# buzzer.net
KiCad netlist of a schematic drawn in Altium Designer
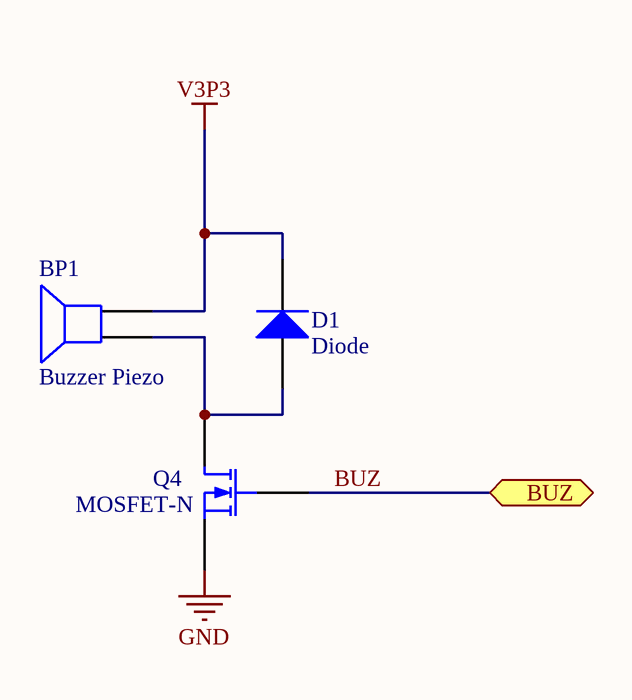
[diagram p0: buzzer.SchDoc]

(export (version "E")
  (design (tool "Eeschema 10.0.6"))
  (components
    (comp (ref "BP1")
      (value "Buzzer Piezo")
      (footprint "BUZZER")
      (description "Buzzer piezo")
      (fields (field (name "PUBLISHER") "Altium Limited"))
      (libsource (lib "Miscellaneous Devices") (part "Speaker"))
    )
    (comp (ref "D1")
      (value "Diode")
      (footprint "PONT REDRESSEUR")
      (description "Default Diode")
      (fields (field (name "PUBLISHER") "Altium Limited"))
      (libsource (lib "Miscellaneous Devices") (part "Diode"))
    )
    (comp (ref "Q4")
      (value "MOSFET-N")
      (footprint "MOSFET")
      (description "N-Channel MOSFET")
      (fields (field (name "PUBLISHER") "Altium Limited"))
      (libsource (lib "Miscellaneous Devices") (part "MOSFET-N"))
    )
  )
  (nets
    (net (code "1") (name "/BUZ") (class "Default")
      (node (ref "Q4") (pin "2") (pinfunction "G_2") (pintype "passive"))
    )
    (net (code "2") (name "GND") (class "Default")
      (node (ref "Q4") (pin "3") (pinfunction "S_3") (pintype "passive"))
    )
    (net (code "3") (name "Net-(D1-A)") (class "Default")
      (node (ref "BP1") (pin "1") (pinfunction "1_1") (pintype "passive"))
      (node (ref "D1") (pin "1") (pinfunction "A_1") (pintype "passive"))
      (node (ref "Q4") (pin "1") (pinfunction "D_1") (pintype "passive"))
    )
    (net (code "4") (name "V3P3") (class "Default")
      (node (ref "BP1") (pin "2") (pinfunction "2_2") (pintype "passive"))
      (node (ref "D1") (pin "2") (pinfunction "K_2") (pintype "passive"))
    )
  )
)
